# Sensor.net
KiCad netlist of a schematic drawn in Altium Designer
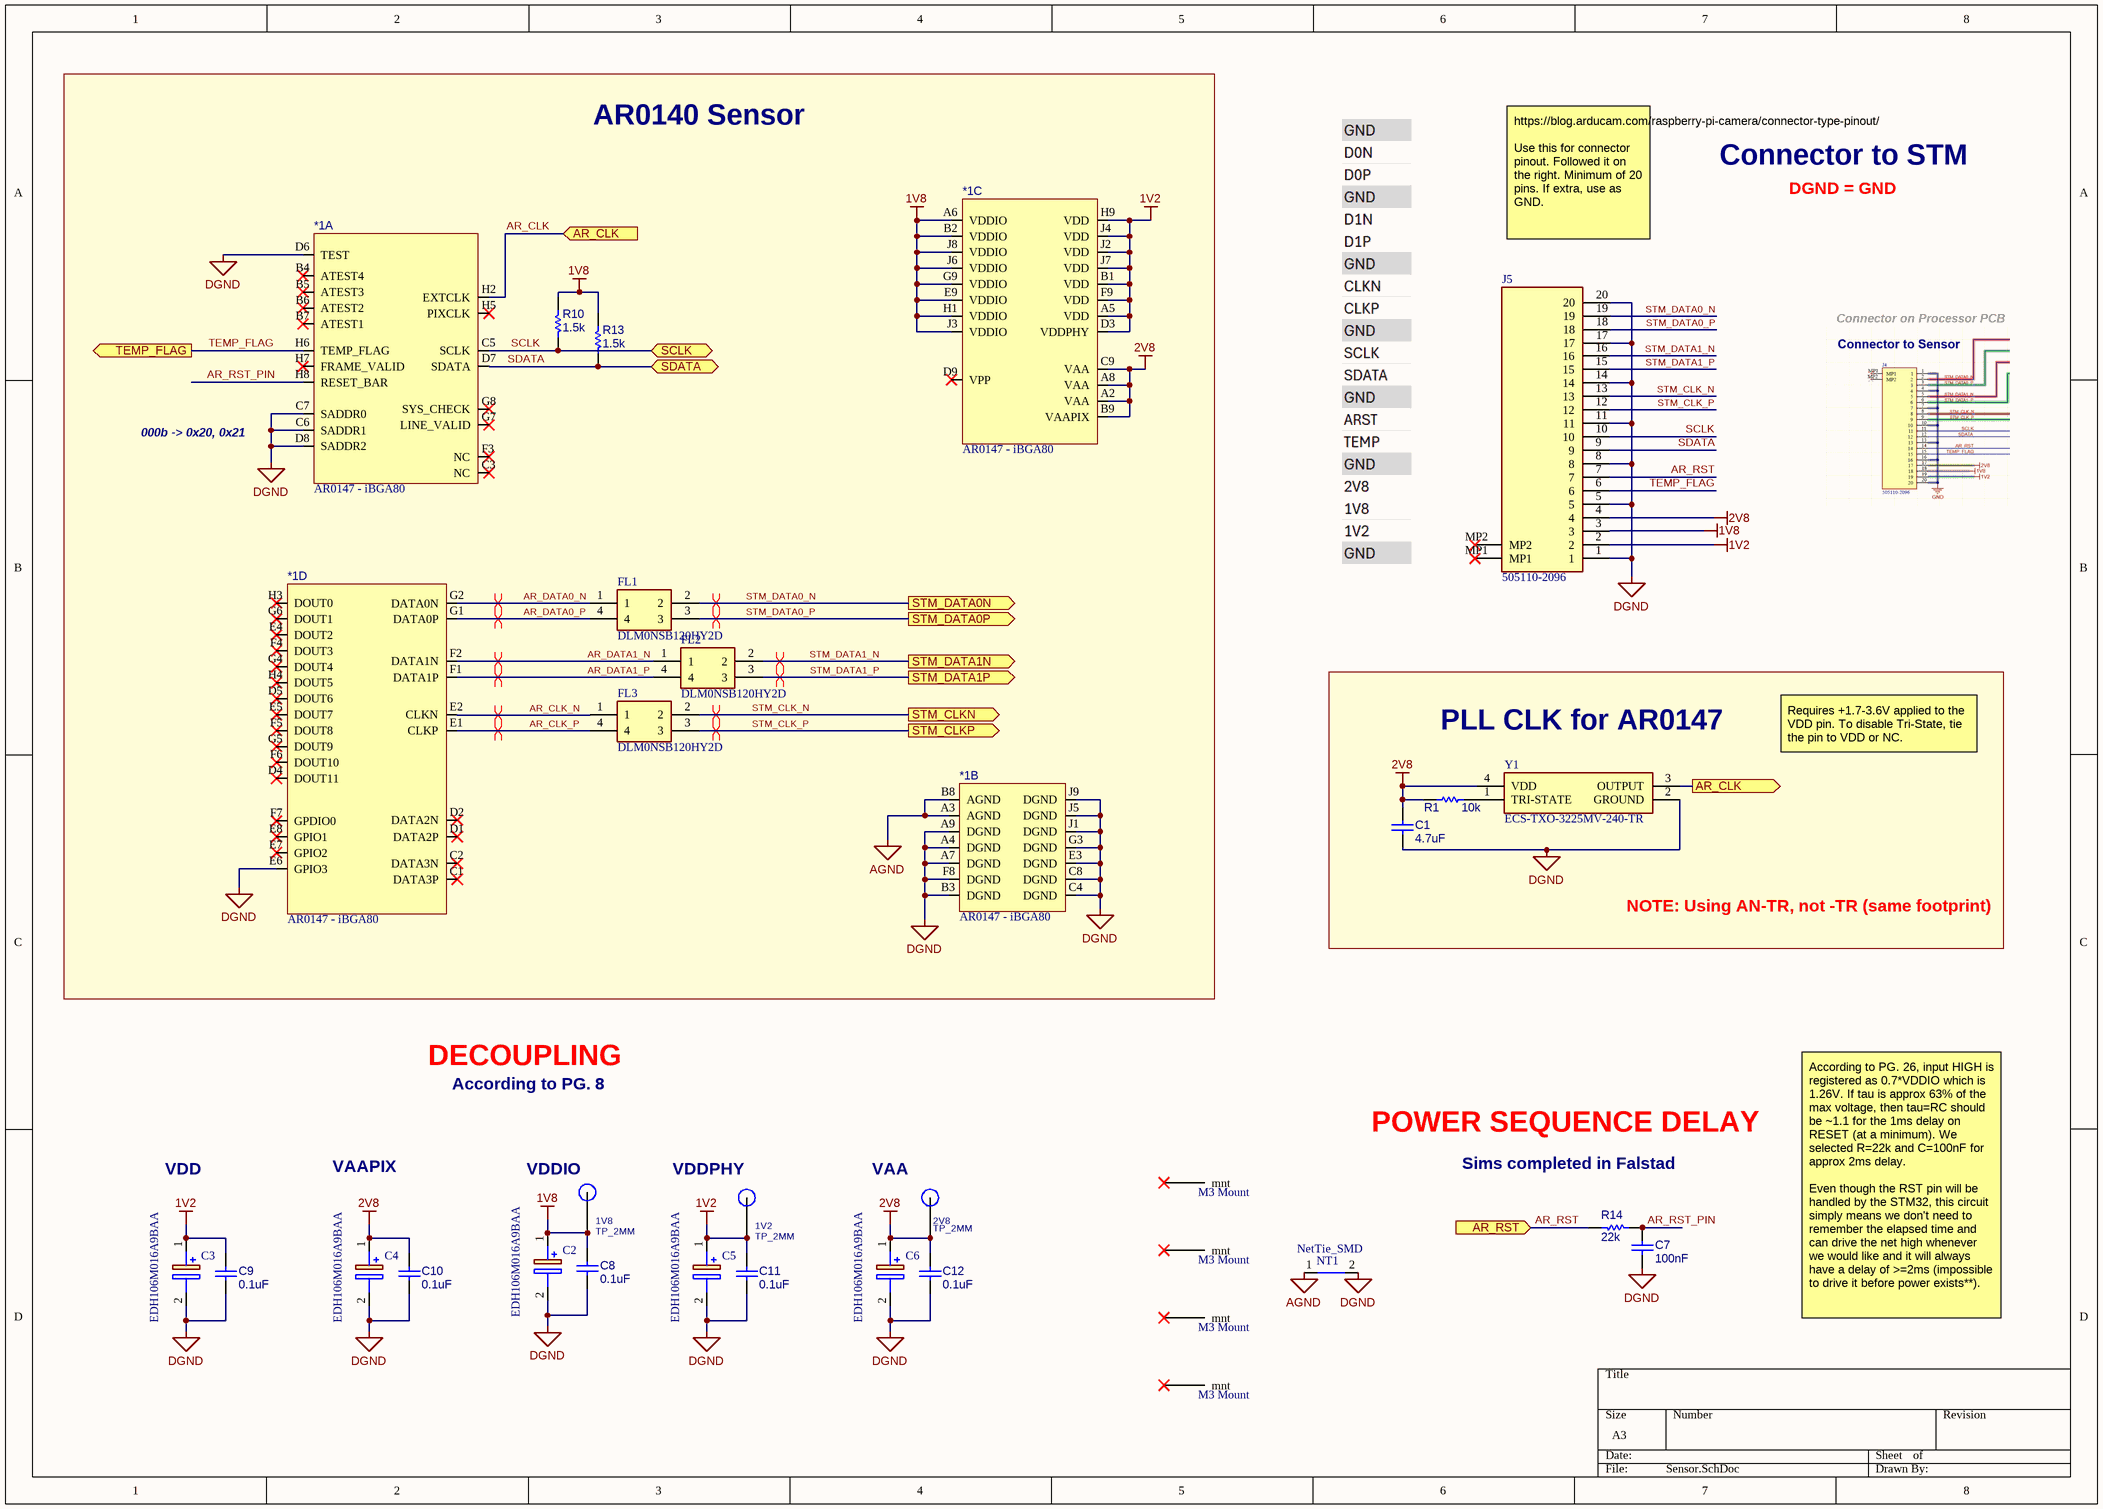
[diagram p0: Sensor.SchDoc]

(export (version "E")
  (design (tool "Eeschema 10.0.6"))
  (components
    (comp (ref "*1")
      (value "AR0147 - iBGA80")
      (footprint "AR0147 - IBGA80")
      (libsource (lib "") (part "AR0147 - iBGA80_1"))
    )
    (comp (ref "1V2")
      (value "TP_2MM")
      (footprint "TESTPOINT 2MM")
      (libsource (lib "C2Sv0 - Processor") (part "TP_2MM"))
    )
    (comp (ref "1V8")
      (value "TP_2MM")
      (footprint "TESTPOINT 2MM")
      (libsource (lib "C2Sv0 - Processor") (part "TP_2MM"))
    )
    (comp (ref "2V8")
      (value "TP_2MM")
      (footprint "TESTPOINT 2MM")
      (libsource (lib "C2Sv0 - Processor") (part "TP_2MM"))
    )
    (comp (ref "C1")
      (value "4.7uF")
      (footprint "C0603")
      (description "Capacitor, MLCC, 100nF, 6V3, X5R, 10%, 0603, T=0,8mm")
      (fields
        (field (name "MANUFACTURER PART NUMBER") "CC0603KRX5R5BB104")
        (field (name "MANUFACTURER") "YAGEO")
        (field (name "PROVIDED_BY") "SUBCO")
      )
      (libsource (lib "Perth Aerospace Student Team") (part "CMP-035-000015-1"))
    )
    (comp (ref "C2")
      (value "EDH106M016A9BAA")
      (footprint "EDH106M016A9BAA")
      (description "Capacitor Polarised")
      (fields (field (name "MOUSER PART NUMBER") "80-EDH106M016A9BAA"))
      (libsource (lib "C2Sv0 - Sensor") (part "EDH106M016A9BAA"))
    )
    (comp (ref "C3")
      (value "EDH106M016A9BAA")
      (footprint "EDH106M016A9BAA")
      (description "Capacitor Polarised")
      (fields (field (name "MOUSER PART NUMBER") "80-EDH106M016A9BAA"))
      (libsource (lib "C2Sv0 - Sensor") (part "EDH106M016A9BAA"))
    )
    (comp (ref "C4")
      (value "EDH106M016A9BAA")
      (footprint "EDH106M016A9BAA")
      (description "Capacitor Polarised")
      (fields (field (name "MOUSER PART NUMBER") "80-EDH106M016A9BAA"))
      (libsource (lib "C2Sv0 - Sensor") (part "EDH106M016A9BAA"))
    )
    (comp (ref "C5")
      (value "EDH106M016A9BAA")
      (footprint "EDH106M016A9BAA")
      (description "Capacitor Polarised")
      (fields (field (name "MOUSER PART NUMBER") "80-EDH106M016A9BAA"))
      (libsource (lib "C2Sv0 - Sensor") (part "EDH106M016A9BAA"))
    )
    (comp (ref "C6")
      (value "EDH106M016A9BAA")
      (footprint "EDH106M016A9BAA")
      (description "Capacitor Polarised")
      (fields (field (name "MOUSER PART NUMBER") "80-EDH106M016A9BAA"))
      (libsource (lib "C2Sv0 - Sensor") (part "EDH106M016A9BAA"))
    )
    (comp (ref "C7")
      (value "100nF")
      (footprint "C0603")
      (description "Capacitor, MLCC, 100nF, 6V3, X5R, 10%, 0603, T=0,8mm")
      (fields
        (field (name "MANUFACTURER PART NUMBER") "CC0603KRX5R5BB104")
        (field (name "MANUFACTURER") "YAGEO")
        (field (name "PROVIDED_BY") "SUBCO")
      )
      (libsource (lib "Perth Aerospace Student Team") (part "CMP-035-000015-1"))
    )
    (comp (ref "C8")
      (value "0.1uF")
      (footprint "C0603")
      (description "Capacitor, MLCC, 100nF, 6V3, X5R, 10%, 0603, T=0,8mm")
      (fields
        (field (name "MANUFACTURER PART NUMBER") "CC0603KRX5R5BB104")
        (field (name "MANUFACTURER") "YAGEO")
        (field (name "PROVIDED_BY") "SUBCO")
      )
      (libsource (lib "Perth Aerospace Student Team") (part "CMP-035-000015-1"))
    )
    (comp (ref "C9")
      (value "0.1uF")
      (footprint "C0603")
      (description "Capacitor, MLCC, 100nF, 6V3, X5R, 10%, 0603, T=0,8mm")
      (fields
        (field (name "MANUFACTURER PART NUMBER") "CC0603KRX5R5BB104")
        (field (name "MANUFACTURER") "YAGEO")
        (field (name "PROVIDED_BY") "SUBCO")
      )
      (libsource (lib "Perth Aerospace Student Team") (part "CMP-035-000015-1"))
    )
    (comp (ref "C10")
      (value "0.1uF")
      (footprint "C0603")
      (description "Capacitor, MLCC, 100nF, 6V3, X5R, 10%, 0603, T=0,8mm")
      (fields
        (field (name "MANUFACTURER PART NUMBER") "CC0603KRX5R5BB104")
        (field (name "MANUFACTURER") "YAGEO")
        (field (name "PROVIDED_BY") "SUBCO")
      )
      (libsource (lib "Perth Aerospace Student Team") (part "CMP-035-000015-1"))
    )
    (comp (ref "C11")
      (value "0.1uF")
      (footprint "C0603")
      (description "Capacitor, MLCC, 100nF, 6V3, X5R, 10%, 0603, T=0,8mm")
      (fields
        (field (name "MANUFACTURER PART NUMBER") "CC0603KRX5R5BB104")
        (field (name "MANUFACTURER") "YAGEO")
        (field (name "PROVIDED_BY") "SUBCO")
      )
      (libsource (lib "Perth Aerospace Student Team") (part "CMP-035-000015-1"))
    )
    (comp (ref "C12")
      (value "0.1uF")
      (footprint "C0603")
      (description "Capacitor, MLCC, 100nF, 6V3, X5R, 10%, 0603, T=0,8mm")
      (fields
        (field (name "MANUFACTURER PART NUMBER") "CC0603KRX5R5BB104")
        (field (name "MANUFACTURER") "YAGEO")
        (field (name "PROVIDED_BY") "SUBCO")
      )
      (libsource (lib "Perth Aerospace Student Team") (part "CMP-035-000015-1"))
    )
    (comp (ref "FL1")
      (value "DLM0NSB120HY2D")
      (footprint "DLM0NSB120HY2D")
      (description "Filter")
      (fields (field (name "MOUSER PART NUMBER") "81-DLM0NSB120HY2D"))
      (libsource (lib "C2Sv0 - Sensor") (part "DLM0NSB120HY2D"))
    )
    (comp (ref "FL2")
      (value "DLM0NSB120HY2D")
      (footprint "DLM0NSB120HY2D")
      (description "Filter")
      (fields (field (name "MOUSER PART NUMBER") "81-DLM0NSB120HY2D"))
      (libsource (lib "C2Sv0 - Sensor") (part "DLM0NSB120HY2D"))
    )
    (comp (ref "FL3")
      (value "DLM0NSB120HY2D")
      (footprint "DLM0NSB120HY2D")
      (description "Filter")
      (fields (field (name "MOUSER PART NUMBER") "81-DLM0NSB120HY2D"))
      (libsource (lib "C2Sv0 - Sensor") (part "DLM0NSB120HY2D"))
    )
    (comp (ref "J5")
      (value "505110-2096")
      (footprint "5051102096")
      (description "Connector")
      (fields (field (name "MOUSER PART NUMBER") "538-505110-2096"))
      (libsource (lib "C2S") (part "505110-2096"))
    )
    (comp (ref "MNT1")
      (value "M3 Mount")
      (footprint "M3_Mount-Footprint-1")
      (description "M3 mounting hole")
      (fields (field (name "AUTHOR") "Raphael Ho"))
      (libsource (lib "Perth Aerospace Student Team") (part "M3_Mount-Symbol-1"))
    )
    (comp (ref "MNT2")
      (value "M3 Mount")
      (footprint "M3_Mount-Footprint-1")
      (description "M3 mounting hole")
      (fields (field (name "AUTHOR") "Raphael Ho"))
      (libsource (lib "Perth Aerospace Student Team") (part "M3_Mount-Symbol-1"))
    )
    (comp (ref "MNT3")
      (value "M3 Mount")
      (footprint "M3_Mount-Footprint-1")
      (description "M3 mounting hole")
      (fields (field (name "AUTHOR") "Raphael Ho"))
      (libsource (lib "Perth Aerospace Student Team") (part "M3_Mount-Symbol-1"))
    )
    (comp (ref "MNT4")
      (value "M3 Mount")
      (footprint "M3_Mount-Footprint-1")
      (description "M3 mounting hole")
      (fields (field (name "AUTHOR") "Raphael Ho"))
      (libsource (lib "Perth Aerospace Student Team") (part "M3_Mount-Symbol-1"))
    )
    (comp (ref "NT1")
      (value "NetTie_SMD")
      (footprint "NETTIE_SMD")
      (description "Net Tie SMD")
      (fields (field (name "SOURCE") "Schematic-Lib-PhilsLab.SchLib"))
      (libsource (lib "Perth Aerospace Student Team") (part "NetTie_SMD"))
    )
    (comp (ref "R1")
      (value "10k")
      (footprint "RESC1608X55X25ML10T15-1")
      (description "Chip Resistor, 10k Ohm, 0.1 W, -55 to 155 degC, 0603 (1608 Metric)")
      (fields
        (field (name "POWER") "100mW")
        (field (name "TOLERANCE") "1%")
        (field (name "CREATED BY") "Micah Randall")
      )
      (libsource (lib "Perth Aerospace Student Team") (part "CMP-009-00006-5"))
    )
    (comp (ref "R10")
      (value "1.5k")
      (footprint "RESC1608X55X25ML10T15-1")
      (description "Chip Resistor, 10k Ohm, 0.1 W, -55 to 155 degC, 0603 (1608 Metric)")
      (fields
        (field (name "POWER") "100mW")
        (field (name "TOLERANCE") "1%")
        (field (name "CREATED BY") "Micah Randall")
      )
      (libsource (lib "Perth Aerospace Student Team") (part "CMP-009-00006-5"))
    )
    (comp (ref "R13")
      (value "1.5k")
      (footprint "RESC1608X55X25ML10T15-1")
      (description "Chip Resistor, 10k Ohm, 0.1 W, -55 to 155 degC, 0603 (1608 Metric)")
      (fields
        (field (name "POWER") "100mW")
        (field (name "TOLERANCE") "1%")
        (field (name "CREATED BY") "Micah Randall")
      )
      (libsource (lib "Perth Aerospace Student Team") (part "CMP-009-00006-5"))
    )
    (comp (ref "R14")
      (value "22k")
      (footprint "RESC1608X55X25ML10T15-1")
      (description "Chip Resistor, 10k Ohm, 0.1 W, -55 to 155 degC, 0603 (1608 Metric)")
      (fields
        (field (name "POWER") "100mW")
        (field (name "TOLERANCE") "1%")
        (field (name "CREATED BY") "Micah Randall")
      )
      (libsource (lib "Perth Aerospace Student Team") (part "CMP-009-00006-5"))
    )
    (comp (ref "Y1")
      (value "ECS-TXO-3225MV-240-TR")
      (footprint "ECSTXO3225MV240TR")
      (description "Crystal or Oscillator")
      (fields (field (name "MOUSER PART NUMBER") "520-TXO-3225MV-240-T"))
      (libsource (lib "C2S") (part "ECS-TXO-3225MV-240-TR"))
    )
  )
  (nets
    (net (code "1") (name "/AR_CLK") (class "Default")
      (node (ref "*1") (pin "H2") (pinfunction "EXTCLK_H2") (pintype "input"))
      (node (ref "Y1") (pin "3") (pinfunction "OUTPUT_3") (pintype "passive"))
    )
    (net (code "2") (name "/AR_CLK_N") (class "Default")
      (node (ref "*1") (pin "E2") (pinfunction "CLKN_E2") (pintype "output"))
      (node (ref "FL3") (pin "1") (pinfunction "1_1") (pintype "passive"))
    )
    (net (code "3") (name "/AR_CLK_P") (class "Default")
      (node (ref "*1") (pin "E1") (pinfunction "CLKP_E1") (pintype "output"))
      (node (ref "FL3") (pin "4") (pinfunction "4_4") (pintype "passive"))
    )
    (net (code "4") (name "/AR_DATA0_N") (class "Default")
      (node (ref "*1") (pin "G2") (pinfunction "DATA0N_G2") (pintype "output"))
      (node (ref "FL1") (pin "1") (pinfunction "1_1") (pintype "passive"))
    )
    (net (code "5") (name "/AR_DATA0_P") (class "Default")
      (node (ref "*1") (pin "G1") (pinfunction "DATA0P_G1") (pintype "output"))
      (node (ref "FL1") (pin "4") (pinfunction "4_4") (pintype "passive"))
    )
    (net (code "6") (name "/AR_DATA1_N") (class "Default")
      (node (ref "*1") (pin "F2") (pinfunction "DATA1N_F2") (pintype "output"))
      (node (ref "FL2") (pin "1") (pinfunction "1_1") (pintype "passive"))
    )
    (net (code "7") (name "/AR_DATA1_P") (class "Default")
      (node (ref "*1") (pin "F1") (pinfunction "DATA1P_F1") (pintype "output"))
      (node (ref "FL2") (pin "4") (pinfunction "4_4") (pintype "passive"))
    )
    (net (code "8") (name "/AR_RST") (class "Default")
      (node (ref "J5") (pin "7") (pinfunction "7_7") (pintype "passive"))
      (node (ref "R14") (pin "1") (pinfunction "1_1") (pintype "passive"))
    )
    (net (code "9") (name "/AR_RST_PIN") (class "Default")
      (node (ref "*1") (pin "H8") (pinfunction "RESET_BAR_H8") (pintype "input"))
      (node (ref "C7") (pin "2") (pinfunction "2_2") (pintype "passive"))
      (node (ref "R14") (pin "2") (pinfunction "2_2") (pintype "passive"))
    )
    (net (code "10") (name "/SCLK") (class "Default")
      (node (ref "*1") (pin "C5") (pinfunction "SCLK_C5") (pintype "input"))
      (node (ref "J5") (pin "10") (pinfunction "10_10") (pintype "passive"))
      (node (ref "R10") (pin "2") (pinfunction "2_2") (pintype "passive"))
    )
    (net (code "11") (name "/SDATA") (class "Default")
      (node (ref "*1") (pin "D7") (pinfunction "SDATA_D7") (pintype "input"))
      (node (ref "J5") (pin "9") (pinfunction "9_9") (pintype "passive"))
      (node (ref "R13") (pin "2") (pinfunction "2_2") (pintype "passive"))
    )
    (net (code "12") (name "/STM_CLK_N") (class "Default")
      (node (ref "FL3") (pin "2") (pinfunction "2_2") (pintype "passive"))
      (node (ref "J5") (pin "13") (pinfunction "13_13") (pintype "passive"))
    )
    (net (code "13") (name "/STM_CLK_P") (class "Default")
      (node (ref "FL3") (pin "3") (pinfunction "3_3") (pintype "passive"))
      (node (ref "J5") (pin "12") (pinfunction "12_12") (pintype "passive"))
    )
    (net (code "14") (name "/STM_DATA0_N") (class "Default")
      (node (ref "FL1") (pin "2") (pinfunction "2_2") (pintype "passive"))
      (node (ref "J5") (pin "19") (pinfunction "19_19") (pintype "passive"))
    )
    (net (code "15") (name "/STM_DATA0_P") (class "Default")
      (node (ref "FL1") (pin "3") (pinfunction "3_3") (pintype "passive"))
      (node (ref "J5") (pin "18") (pinfunction "18_18") (pintype "passive"))
    )
    (net (code "16") (name "/STM_DATA1_N") (class "Default")
      (node (ref "FL2") (pin "2") (pinfunction "2_2") (pintype "passive"))
      (node (ref "J5") (pin "16") (pinfunction "16_16") (pintype "passive"))
    )
    (net (code "17") (name "/STM_DATA1_P") (class "Default")
      (node (ref "FL2") (pin "3") (pinfunction "3_3") (pintype "passive"))
      (node (ref "J5") (pin "15") (pinfunction "15_15") (pintype "passive"))
    )
    (net (code "18") (name "/TEMP_FLAG") (class "Default")
      (node (ref "*1") (pin "H6") (pinfunction "TEMP_FLAG_H6") (pintype "output"))
      (node (ref "J5") (pin "6") (pinfunction "6_6") (pintype "passive"))
    )
    (net (code "19") (name "1V2") (class "Default")
      (node (ref "*1") (pin "A5") (pinfunction "VDD_A5") (pintype "power_in"))
      (node (ref "*1") (pin "B1") (pinfunction "VDD_B1") (pintype "power_in"))
      (node (ref "*1") (pin "D3") (pinfunction "VDDPHY_D3") (pintype "power_in"))
      (node (ref "*1") (pin "F9") (pinfunction "VDD_F9") (pintype "power_in"))
      (node (ref "*1") (pin "H9") (pinfunction "VDD_H9") (pintype "power_in"))
      (node (ref "*1") (pin "J2") (pinfunction "VDD_J2") (pintype "power_in"))
      (node (ref "*1") (pin "J4") (pinfunction "VDD_J4") (pintype "power_in"))
      (node (ref "*1") (pin "J7") (pinfunction "VDD_J7") (pintype "power_in"))
      (node (ref "1V2") (pin "TP") (pinfunction "TP_2MM_TP") (pintype "passive"))
      (node (ref "C11") (pin "2") (pinfunction "2_2") (pintype "passive"))
      (node (ref "C3") (pin "1") (pinfunction "+_1") (pintype "passive"))
      (node (ref "C5") (pin "1") (pinfunction "+_1") (pintype "passive"))
      (node (ref "C9") (pin "2") (pinfunction "2_2") (pintype "passive"))
      (node (ref "J5") (pin "2") (pinfunction "2_2") (pintype "passive"))
    )
    (net (code "20") (name "1V8") (class "Default")
      (node (ref "*1") (pin "A6") (pinfunction "VDDIO_A6") (pintype "power_in"))
      (node (ref "*1") (pin "B2") (pinfunction "VDDIO_B2") (pintype "power_in"))
      (node (ref "*1") (pin "E9") (pinfunction "VDDIO_E9") (pintype "power_in"))
      (node (ref "*1") (pin "G9") (pinfunction "VDDIO_G9") (pintype "power_in"))
      (node (ref "*1") (pin "H1") (pinfunction "VDDIO_H1") (pintype "power_in"))
      (node (ref "*1") (pin "J3") (pinfunction "VDDIO_J3") (pintype "power_in"))
      (node (ref "*1") (pin "J6") (pinfunction "VDDIO_J6") (pintype "power_in"))
      (node (ref "*1") (pin "J8") (pinfunction "VDDIO_J8") (pintype "power_in"))
      (node (ref "1V8") (pin "TP") (pinfunction "TP_2MM_TP") (pintype "passive"))
      (node (ref "C2") (pin "1") (pinfunction "+_1") (pintype "passive"))
      (node (ref "C8") (pin "2") (pinfunction "2_2") (pintype "passive"))
      (node (ref "J5") (pin "3") (pinfunction "3_3") (pintype "passive"))
      (node (ref "R10") (pin "1") (pinfunction "1_1") (pintype "passive"))
      (node (ref "R13") (pin "1") (pinfunction "1_1") (pintype "passive"))
    )
    (net (code "21") (name "2V8") (class "Default")
      (node (ref "*1") (pin "A2") (pinfunction "VAA_A2") (pintype "power_in"))
      (node (ref "*1") (pin "A8") (pinfunction "VAA_A8") (pintype "power_in"))
      (node (ref "*1") (pin "B9") (pinfunction "VAAPIX_B9") (pintype "power_in"))
      (node (ref "*1") (pin "C9") (pinfunction "VAA_C9") (pintype "power_in"))
      (node (ref "2V8") (pin "TP") (pinfunction "TP_2MM_TP") (pintype "passive"))
      (node (ref "C1") (pin "2") (pinfunction "2_2") (pintype "passive"))
      (node (ref "C10") (pin "2") (pinfunction "2_2") (pintype "passive"))
      (node (ref "C12") (pin "2") (pinfunction "2_2") (pintype "passive"))
      (node (ref "C4") (pin "1") (pinfunction "+_1") (pintype "passive"))
      (node (ref "C6") (pin "1") (pinfunction "+_1") (pintype "passive"))
      (node (ref "J5") (pin "4") (pinfunction "4_4") (pintype "passive"))
      (node (ref "R1") (pin "1") (pinfunction "1_1") (pintype "passive"))
      (node (ref "Y1") (pin "4") (pinfunction "VDD_4") (pintype "passive"))
    )
    (net (code "22") (name "AGND") (class "Default")
      (node (ref "*1") (pin "A3") (pinfunction "AGND_A3") (pintype "power_in"))
      (node (ref "*1") (pin "B8") (pinfunction "AGND_B8") (pintype "power_in"))
      (node (ref "NT1") (pin "1") (pinfunction "1_1") (pintype "passive"))
    )
    (net (code "23") (name "DGND") (class "Default")
      (node (ref "*1") (pin "A4") (pinfunction "DGND_A4") (pintype "power_in"))
      (node (ref "*1") (pin "A7") (pinfunction "DGND_A7") (pintype "power_in"))
      (node (ref "*1") (pin "A9") (pinfunction "DGND_A9") (pintype "power_in"))
      (node (ref "*1") (pin "B3") (pinfunction "DGND_B3") (pintype "power_in"))
      (node (ref "*1") (pin "C4") (pinfunction "DGND_C4") (pintype "power_in"))
      (node (ref "*1") (pin "C6") (pinfunction "SADDR1_C6") (pintype "input"))
      (node (ref "*1") (pin "C7") (pinfunction "SADDR0_C7") (pintype "input"))
      (node (ref "*1") (pin "C8") (pinfunction "DGND_C8") (pintype "power_in"))
      (node (ref "*1") (pin "D6") (pinfunction "TEST_D6") (pintype "passive"))
      (node (ref "*1") (pin "D8") (pinfunction "SADDR2_D8") (pintype "input"))
      (node (ref "*1") (pin "E3") (pinfunction "DGND_E3") (pintype "power_in"))
      (node (ref "*1") (pin "E6") (pinfunction "GPIO3_E6") (pintype "bidirectional"))
      (node (ref "*1") (pin "F8") (pinfunction "DGND_F8") (pintype "power_in"))
      (node (ref "*1") (pin "G3") (pinfunction "DGND_G3") (pintype "power_in"))
      (node (ref "*1") (pin "J1") (pinfunction "DGND_J1") (pintype "power_in"))
      (node (ref "*1") (pin "J5") (pinfunction "DGND_J5") (pintype "power_in"))
      (node (ref "*1") (pin "J9") (pinfunction "DGND_J9") (pintype "power_in"))
      (node (ref "C1") (pin "1") (pinfunction "1_1") (pintype "passive"))
      (node (ref "C10") (pin "1") (pinfunction "1_1") (pintype "passive"))
      (node (ref "C11") (pin "1") (pinfunction "1_1") (pintype "passive"))
      (node (ref "C12") (pin "1") (pinfunction "1_1") (pintype "passive"))
      (node (ref "C2") (pin "2") (pinfunction "-_2") (pintype "passive"))
      (node (ref "C3") (pin "2") (pinfunction "-_2") (pintype "passive"))
      (node (ref "C4") (pin "2") (pinfunction "-_2") (pintype "passive"))
      (node (ref "C5") (pin "2") (pinfunction "-_2") (pintype "passive"))
      (node (ref "C6") (pin "2") (pinfunction "-_2") (pintype "passive"))
      (node (ref "C7") (pin "1") (pinfunction "1_1") (pintype "passive"))
      (node (ref "C8") (pin "1") (pinfunction "1_1") (pintype "passive"))
      (node (ref "C9") (pin "1") (pinfunction "1_1") (pintype "passive"))
      (node (ref "J5") (pin "1") (pinfunction "1_1") (pintype "passive"))
      (node (ref "J5") (pin "11") (pinfunction "11_11") (pintype "passive"))
      (node (ref "J5") (pin "14") (pinfunction "14_14") (pintype "passive"))
      (node (ref "J5") (pin "17") (pinfunction "17_17") (pintype "passive"))
      (node (ref "J5") (pin "20") (pinfunction "20_20") (pintype "passive"))
      (node (ref "J5") (pin "5") (pinfunction "5_5") (pintype "passive"))
      (node (ref "J5") (pin "8") (pinfunction "8_8") (pintype "passive"))
      (node (ref "NT1") (pin "2") (pinfunction "2_2") (pintype "passive"))
      (node (ref "Y1") (pin "2") (pinfunction "GROUND_2") (pintype "passive"))
    )
    (net (code "24") (name "Net-(Y1-TRI-STATE)") (class "Default")
      (node (ref "R1") (pin "2") (pinfunction "2_2") (pintype "passive"))
      (node (ref "Y1") (pin "1") (pinfunction "TRI-STATE_1") (pintype "passive"))
    )
    (net (code "25") (name "unconnected-(*1A-ATEST1-PadB7)") (class "Default")
      (node (ref "*1") (pin "B7") (pinfunction "ATEST1_B7") (pintype "passive+no_connect"))
    )
    (net (code "26") (name "unconnected-(*1A-ATEST2-PadB6)") (class "Default")
      (node (ref "*1") (pin "B6") (pinfunction "ATEST2_B6") (pintype "passive+no_connect"))
    )
    (net (code "27") (name "unconnected-(*1A-ATEST3-PadB5)") (class "Default")
      (node (ref "*1") (pin "B5") (pinfunction "ATEST3_B5") (pintype "passive+no_connect"))
    )
    (net (code "28") (name "unconnected-(*1A-ATEST4-PadB4)") (class "Default")
      (node (ref "*1") (pin "B4") (pinfunction "ATEST4_B4") (pintype "passive+no_connect"))
    )
    (net (code "29") (name "unconnected-(*1A-FRAME_VALID-PadH7)") (class "Default")
      (node (ref "*1") (pin "H7") (pinfunction "FRAME_VALID_H7") (pintype "output+no_connect"))
    )
    (net (code "30") (name "unconnected-(*1A-LINE_VALID-PadG7)") (class "Default")
      (node (ref "*1") (pin "G7") (pinfunction "LINE_VALID_G7") (pintype "output+no_connect"))
    )
    (net (code "31") (name "unconnected-(*1A-NC-PadC3)") (class "Default")
      (node (ref "*1") (pin "C3") (pinfunction "NC_C3") (pintype "passive+no_connect"))
    )
    (net (code "32") (name "unconnected-(*1A-NC-PadF3)") (class "Default")
      (node (ref "*1") (pin "F3") (pinfunction "NC_F3") (pintype "passive+no_connect"))
    )
    (net (code "33") (name "unconnected-(*1A-PIXCLK-PadH5)") (class "Default")
      (node (ref "*1") (pin "H5") (pinfunction "PIXCLK_H5") (pintype "output+no_connect"))
    )
    (net (code "34") (name "unconnected-(*1A-SYS_CHECK-PadG8)") (class "Default")
      (node (ref "*1") (pin "G8") (pinfunction "SYS_CHECK_G8") (pintype "output+no_connect"))
    )
    (net (code "35") (name "unconnected-(*1C-VPP-PadD9)") (class "Default")
      (node (ref "*1") (pin "D9") (pinfunction "VPP_D9") (pintype "power_in+no_connect"))
    )
    (net (code "36") (name "unconnected-(*1D-DATA2N-PadD2)") (class "Default")
      (node (ref "*1") (pin "D2") (pinfunction "DATA2N_D2") (pintype "output+no_connect"))
    )
    (net (code "37") (name "unconnected-(*1D-DATA2P-PadD1)") (class "Default")
      (node (ref "*1") (pin "D1") (pinfunction "DATA2P_D1") (pintype "output+no_connect"))
    )
    (net (code "38") (name "unconnected-(*1D-DATA3N-PadC2)") (class "Default")
      (node (ref "*1") (pin "C2") (pinfunction "DATA3N_C2") (pintype "output+no_connect"))
    )
    (net (code "39") (name "unconnected-(*1D-DATA3P-PadC1)") (class "Default")
      (node (ref "*1") (pin "C1") (pinfunction "DATA3P_C1") (pintype "output+no_connect"))
    )
    (net (code "40") (name "unconnected-(*1D-DOUT0-PadH3)") (class "Default")
      (node (ref "*1") (pin "H3") (pinfunction "DOUT0_H3") (pintype "output+no_connect"))
    )
    (net (code "41") (name "unconnected-(*1D-DOUT1-PadG6)") (class "Default")
      (node (ref "*1") (pin "G6") (pinfunction "DOUT1_G6") (pintype "output+no_connect"))
    )
    (net (code "42") (name "unconnected-(*1D-DOUT2-PadE4)") (class "Default")
      (node (ref "*1") (pin "E4") (pinfunction "DOUT2_E4") (pintype "output+no_connect"))
    )
    (net (code "43") (name "unconnected-(*1D-DOUT3-PadF4)") (class "Default")
      (node (ref "*1") (pin "F4") (pinfunction "DOUT3_F4") (pintype "output+no_connect"))
    )
    (net (code "44") (name "unconnected-(*1D-DOUT4-PadG4)") (class "Default")
      (node (ref "*1") (pin "G4") (pinfunction "DOUT4_G4") (pintype "output+no_connect"))
    )
    (net (code "45") (name "unconnected-(*1D-DOUT5-PadH4)") (class "Default")
      (node (ref "*1") (pin "H4") (pinfunction "DOUT5_H4") (pintype "output+no_connect"))
    )
    (net (code "46") (name "unconnected-(*1D-DOUT6-PadD5)") (class "Default")
      (node (ref "*1") (pin "D5") (pinfunction "DOUT6_D5") (pintype "output+no_connect"))
    )
    (net (code "47") (name "unconnected-(*1D-DOUT7-PadE5)") (class "Default")
      (node (ref "*1") (pin "E5") (pinfunction "DOUT7_E5") (pintype "output+no_connect"))
    )
    (net (code "48") (name "unconnected-(*1D-DOUT8-PadF5)") (class "Default")
      (node (ref "*1") (pin "F5") (pinfunction "DOUT8_F5") (pintype "output+no_connect"))
    )
    (net (code "49") (name "unconnected-(*1D-DOUT9-PadG5)") (class "Default")
      (node (ref "*1") (pin "G5") (pinfunction "DOUT9_G5") (pintype "output+no_connect"))
    )
    (net (code "50") (name "unconnected-(*1D-DOUT10-PadF6)") (class "Default")
      (node (ref "*1") (pin "F6") (pinfunction "DOUT10_F6") (pintype "output+no_connect"))
    )
    (net (code "51") (name "unconnected-(*1D-DOUT11-PadD4)") (class "Default")
      (node (ref "*1") (pin "D4") (pinfunction "DOUT11_D4") (pintype "output+no_connect"))
    )
    (net (code "52") (name "unconnected-(*1D-GPDIO0-PadF7)") (class "Default")
      (node (ref "*1") (pin "F7") (pinfunction "GPDIO0_F7") (pintype "bidirectional+no_connect"))
    )
    (net (code "53") (name "unconnected-(*1D-GPIO1-PadE8)") (class "Default")
      (node (ref "*1") (pin "E8") (pinfunction "GPIO1_E8") (pintype "bidirectional+no_connect"))
    )
    (net (code "54") (name "unconnected-(*1D-GPIO2-PadE7)") (class "Default")
      (node (ref "*1") (pin "E7") (pinfunction "GPIO2_E7") (pintype "bidirectional+no_connect"))
    )
    (net (code "55") (name "unconnected-(J5-PadMP1)") (class "Default")
      (node (ref "J5") (pin "MP1") (pinfunction "MP1_MP1") (pintype "passive+no_connect"))
    )
    (net (code "56") (name "unconnected-(J5-PadMP2)") (class "Default")
      (node (ref "J5") (pin "MP2") (pinfunction "MP2_MP2") (pintype "passive+no_connect"))
    )
    (net (code "57") (name "unconnected-(MNT1-mnt-Pad1)") (class "Default")
      (node (ref "MNT1") (pin "1") (pinfunction "mnt_1") (pintype "passive+no_connect"))
    )
    (net (code "58") (name "unconnected-(MNT2-mnt-Pad1)") (class "Default")
      (node (ref "MNT2") (pin "1") (pinfunction "mnt_1") (pintype "passive+no_connect"))
    )
    (net (code "59") (name "unconnected-(MNT3-mnt-Pad1)") (class "Default")
      (node (ref "MNT3") (pin "1") (pinfunction "mnt_1") (pintype "passive+no_connect"))
    )
    (net (code "60") (name "unconnected-(MNT4-mnt-Pad1)") (class "Default")
      (node (ref "MNT4") (pin "1") (pinfunction "mnt_1") (pintype "passive+no_connect"))
    )
  )
)
